# Buzzer_piezo_PB1475.net
KiCad netlist of a schematic drawn in Altium Designer
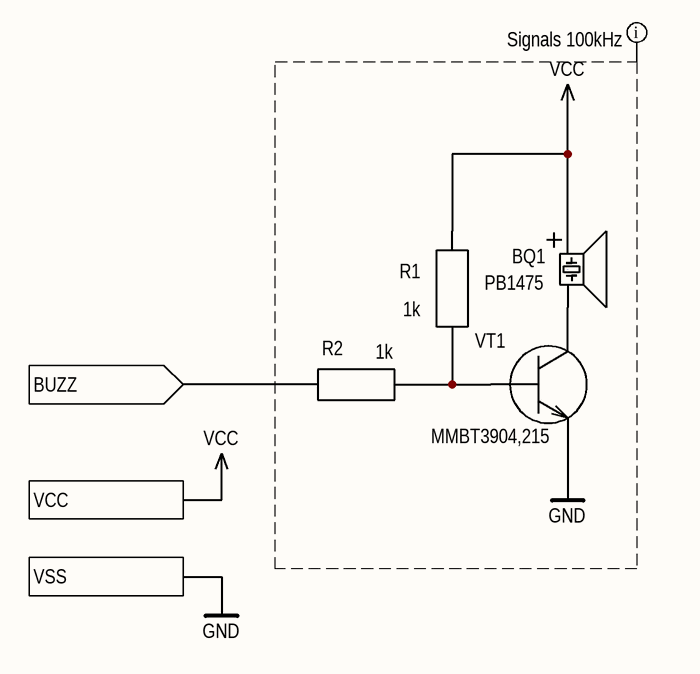
[diagram p0: Buzzer piezo PB1475.SchDoc]

(export (version "E")
  (design (tool "Eeschema 10.0.6"))
  (components
    (comp (ref "BQ1")
      (value "PB1475")
      (footprint "BUZ-D14x7.5N")
      (description "Buzzer d14x7.5 TH")
      (fields (field (name "MANUFACTURER") "SWT"))
      (libsource (lib "Sound") (part "PB1475"))
    )
    (comp (ref "R1")
      (value "1k")
      (footprint "RESC2012N")
      (description "RESC 1k 0805(2012)")
      (fields (field (name "MANUFACTURER") "Yageo") (field (name "TOLERANCE") "±5%"))
      (libsource (lib "Resistors Ceramic SMD 2012") (part "RC0805JR-071KL"))
    )
    (comp (ref "R2")
      (value "1k")
      (footprint "RESC2012N")
      (description "RESC 1k 0805(2012)")
      (fields (field (name "MANUFACTURER") "Yageo") (field (name "TOLERANCE") "±5%"))
      (libsource (lib "Resistors Ceramic SMD 2012") (part "RC0805JR-071KL"))
    )
    (comp (ref "VT1")
      (value "MMBT3904,215")
      (footprint "SOT-23-3N")
      (description "BJT NPN 0.2A 40V")
      (fields (field (name "MANUFACTURER") "NXP Semiconductors") (field (name "POWER") "250mW"))
      (libsource (lib "Transistors BJT") (part "MMBT3904,215"))
    )
  )
  (nets
    (net (code "1") (name "/BUZZ") (class "Default")
      (node (ref "R2") (pin "1") (pinfunction "1_1") (pintype "passive"))
    )
    (net (code "2") (name "GND") (class "Default")
      (node (ref "VT1") (pin "2") (pinfunction "Emitter_2") (pintype "passive"))
    )
    (net (code "3") (name "Net-(BQ1--)") (class "Default")
      (node (ref "BQ1") (pin "2") (pinfunction "-_2") (pintype "passive"))
      (node (ref "VT1") (pin "3") (pinfunction "Collector_3") (pintype "passive"))
    )
    (net (code "4") (name "Net-(VT1-Base)") (class "Default")
      (node (ref "R1") (pin "2") (pinfunction "2_2") (pintype "passive"))
      (node (ref "R2") (pin "2") (pinfunction "2_2") (pintype "passive"))
      (node (ref "VT1") (pin "1") (pinfunction "Base_1") (pintype "passive"))
    )
    (net (code "5") (name "VCC") (class "Default")
      (node (ref "BQ1") (pin "1") (pinfunction "+_1") (pintype "passive"))
      (node (ref "R1") (pin "1") (pinfunction "1_1") (pintype "passive"))
    )
  )
)
